# FPGAPower.net
KiCad netlist of a schematic drawn in Altium Designer
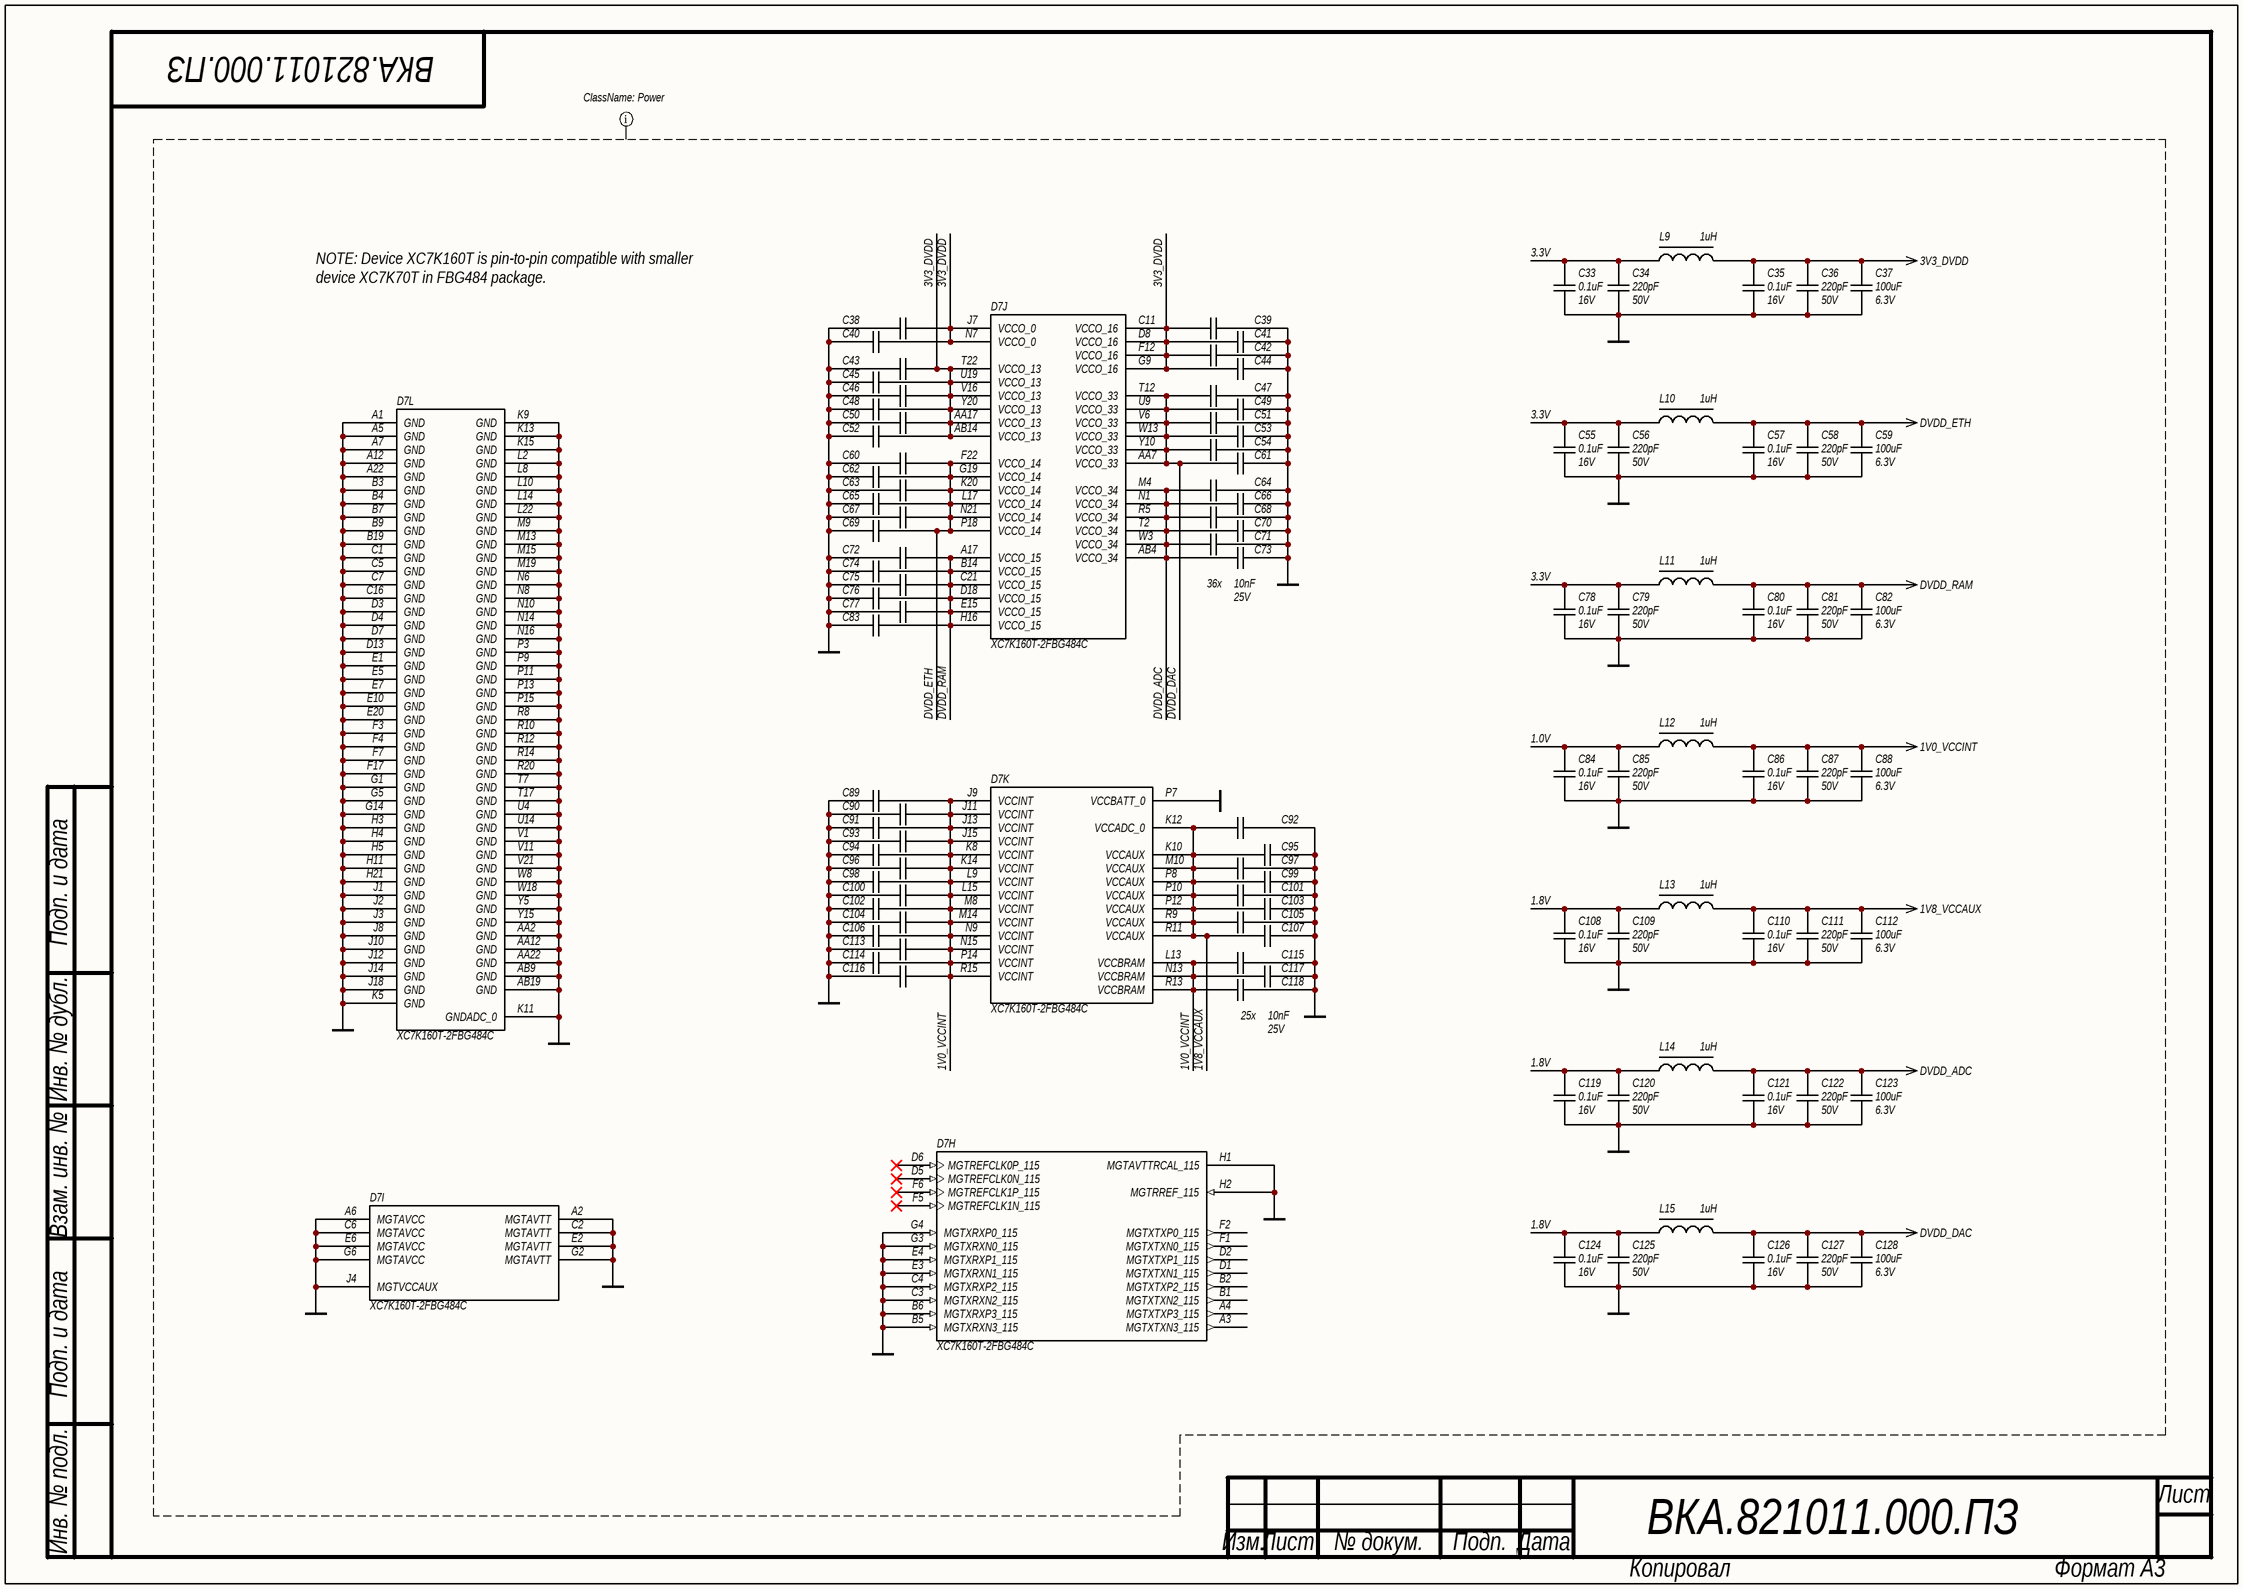
[diagram p0: FPGAPower.SchDoc]

(export (version "E")
  (design (tool "Eeschema 10.0.6"))
  (components
    (comp (ref "C33")
      (value "0.1uF")
      (footprint "C0603")
      (description "SMD Capacitor")
      (fields
        (field (name "MANUFACTURER") "Murata")
        (field (name "TOLERANCE") "10%")
        (field (name "VOLTAGE") "16V")
      )
      (libsource (lib "Kintex_SDR") (part "CAP"))
    )
    (comp (ref "C34")
      (value "220pF")
      (footprint "C0603")
      (description "SMD Capacitor")
      (fields
        (field (name "MANUFACTURER") "Murata")
        (field (name "TOLERANCE") "10%")
        (field (name "VOLTAGE") "50V")
      )
      (libsource (lib "Kintex_SDR") (part "CAP"))
    )
    (comp (ref "C35")
      (value "0.1uF")
      (footprint "C0603")
      (description "SMD Capacitor")
      (fields
        (field (name "MANUFACTURER") "Murata")
        (field (name "TOLERANCE") "10%")
        (field (name "VOLTAGE") "16V")
      )
      (libsource (lib "Kintex_SDR") (part "CAP"))
    )
    (comp (ref "C36")
      (value "220pF")
      (footprint "C0603")
      (description "SMD Capacitor")
      (fields
        (field (name "MANUFACTURER") "Murata")
        (field (name "TOLERANCE") "10%")
        (field (name "VOLTAGE") "50V")
      )
      (libsource (lib "Kintex_SDR") (part "CAP"))
    )
    (comp (ref "C37")
      (value "100uF")
      (footprint "C1210")
      (description "SMD Capacitor")
      (fields
        (field (name "MANUFACTURER") "Murata")
        (field (name "TOLERANCE") "20%")
        (field (name "VOLTAGE") "6.3V")
      )
      (libsource (lib "Kintex_SDR") (part "CAP uF"))
    )
    (comp (ref "C38")
      (value "CAP")
      (footprint "C0402")
      (description "SMD Capacitor")
      (fields (field (name "MANUFACTURER") "Murata") (field (name "TOLERANCE") "10%"))
      (libsource (lib "Kintex_SDR") (part "CAP"))
    )
    (comp (ref "C39")
      (value "CAP")
      (footprint "C0402")
      (description "SMD Capacitor")
      (fields (field (name "MANUFACTURER") "Murata") (field (name "TOLERANCE") "10%"))
      (libsource (lib "Kintex_SDR") (part "CAP"))
    )
    (comp (ref "C40")
      (value "CAP")
      (footprint "C0402")
      (description "SMD Capacitor")
      (fields (field (name "MANUFACTURER") "Murata") (field (name "TOLERANCE") "10%"))
      (libsource (lib "Kintex_SDR") (part "CAP"))
    )
    (comp (ref "C41")
      (value "CAP")
      (footprint "C0402")
      (description "SMD Capacitor")
      (fields (field (name "MANUFACTURER") "Murata") (field (name "TOLERANCE") "10%"))
      (libsource (lib "Kintex_SDR") (part "CAP"))
    )
    (comp (ref "C42")
      (value "CAP")
      (footprint "C0402")
      (description "SMD Capacitor")
      (fields (field (name "MANUFACTURER") "Murata") (field (name "TOLERANCE") "10%"))
      (libsource (lib "Kintex_SDR") (part "CAP"))
    )
    (comp (ref "C43")
      (value "CAP")
      (footprint "C0402")
      (description "SMD Capacitor")
      (fields (field (name "MANUFACTURER") "Murata") (field (name "TOLERANCE") "10%"))
      (libsource (lib "Kintex_SDR") (part "CAP"))
    )
    (comp (ref "C44")
      (value "CAP")
      (footprint "C0402")
      (description "SMD Capacitor")
      (fields (field (name "MANUFACTURER") "Murata") (field (name "TOLERANCE") "10%"))
      (libsource (lib "Kintex_SDR") (part "CAP"))
    )
    (comp (ref "C45")
      (value "CAP")
      (footprint "C0402")
      (description "SMD Capacitor")
      (fields (field (name "MANUFACTURER") "Murata") (field (name "TOLERANCE") "10%"))
      (libsource (lib "Kintex_SDR") (part "CAP"))
    )
    (comp (ref "C46")
      (value "CAP")
      (footprint "C0402")
      (description "SMD Capacitor")
      (fields (field (name "MANUFACTURER") "Murata") (field (name "TOLERANCE") "10%"))
      (libsource (lib "Kintex_SDR") (part "CAP"))
    )
    (comp (ref "C47")
      (value "CAP")
      (footprint "C0402")
      (description "SMD Capacitor")
      (fields (field (name "MANUFACTURER") "Murata") (field (name "TOLERANCE") "10%"))
      (libsource (lib "Kintex_SDR") (part "CAP"))
    )
    (comp (ref "C48")
      (value "CAP")
      (footprint "C0402")
      (description "SMD Capacitor")
      (fields (field (name "MANUFACTURER") "Murata") (field (name "TOLERANCE") "10%"))
      (libsource (lib "Kintex_SDR") (part "CAP"))
    )
    (comp (ref "C49")
      (value "CAP")
      (footprint "C0402")
      (description "SMD Capacitor")
      (fields (field (name "MANUFACTURER") "Murata") (field (name "TOLERANCE") "10%"))
      (libsource (lib "Kintex_SDR") (part "CAP"))
    )
    (comp (ref "C50")
      (value "CAP")
      (footprint "C0402")
      (description "SMD Capacitor")
      (fields (field (name "MANUFACTURER") "Murata") (field (name "TOLERANCE") "10%"))
      (libsource (lib "Kintex_SDR") (part "CAP"))
    )
    (comp (ref "C51")
      (value "CAP")
      (footprint "C0402")
      (description "SMD Capacitor")
      (fields (field (name "MANUFACTURER") "Murata") (field (name "TOLERANCE") "10%"))
      (libsource (lib "Kintex_SDR") (part "CAP"))
    )
    (comp (ref "C52")
      (value "CAP")
      (footprint "C0402")
      (description "SMD Capacitor")
      (fields (field (name "MANUFACTURER") "Murata") (field (name "TOLERANCE") "10%"))
      (libsource (lib "Kintex_SDR") (part "CAP"))
    )
    (comp (ref "C53")
      (value "CAP")
      (footprint "C0402")
      (description "SMD Capacitor")
      (fields (field (name "MANUFACTURER") "Murata") (field (name "TOLERANCE") "10%"))
      (libsource (lib "Kintex_SDR") (part "CAP"))
    )
    (comp (ref "C54")
      (value "CAP")
      (footprint "C0402")
      (description "SMD Capacitor")
      (fields (field (name "MANUFACTURER") "Murata") (field (name "TOLERANCE") "10%"))
      (libsource (lib "Kintex_SDR") (part "CAP"))
    )
    (comp (ref "C55")
      (value "0.1uF")
      (footprint "C0603")
      (description "SMD Capacitor")
      (fields
        (field (name "MANUFACTURER") "Murata")
        (field (name "TOLERANCE") "10%")
        (field (name "VOLTAGE") "16V")
      )
      (libsource (lib "Kintex_SDR") (part "CAP"))
    )
    (comp (ref "C56")
      (value "220pF")
      (footprint "C0603")
      (description "SMD Capacitor")
      (fields
        (field (name "MANUFACTURER") "Murata")
        (field (name "TOLERANCE") "10%")
        (field (name "VOLTAGE") "50V")
      )
      (libsource (lib "Kintex_SDR") (part "CAP"))
    )
    (comp (ref "C57")
      (value "0.1uF")
      (footprint "C0603")
      (description "SMD Capacitor")
      (fields
        (field (name "MANUFACTURER") "Murata")
        (field (name "TOLERANCE") "10%")
        (field (name "VOLTAGE") "16V")
      )
      (libsource (lib "Kintex_SDR") (part "CAP"))
    )
    (comp (ref "C58")
      (value "220pF")
      (footprint "C0603")
      (description "SMD Capacitor")
      (fields
        (field (name "MANUFACTURER") "Murata")
        (field (name "TOLERANCE") "10%")
        (field (name "VOLTAGE") "50V")
      )
      (libsource (lib "Kintex_SDR") (part "CAP"))
    )
    (comp (ref "C59")
      (value "100uF")
      (footprint "C1210")
      (description "SMD Capacitor")
      (fields
        (field (name "MANUFACTURER") "Murata")
        (field (name "TOLERANCE") "20%")
        (field (name "VOLTAGE") "6.3V")
      )
      (libsource (lib "Kintex_SDR") (part "CAP uF"))
    )
    (comp (ref "C60")
      (value "CAP")
      (footprint "C0402")
      (description "SMD Capacitor")
      (fields (field (name "MANUFACTURER") "Murata") (field (name "TOLERANCE") "10%"))
      (libsource (lib "Kintex_SDR") (part "CAP"))
    )
    (comp (ref "C61")
      (value "CAP")
      (footprint "C0402")
      (description "SMD Capacitor")
      (fields (field (name "MANUFACTURER") "Murata") (field (name "TOLERANCE") "10%"))
      (libsource (lib "Kintex_SDR") (part "CAP"))
    )
    (comp (ref "C62")
      (value "CAP")
      (footprint "C0402")
      (description "SMD Capacitor")
      (fields (field (name "MANUFACTURER") "Murata") (field (name "TOLERANCE") "10%"))
      (libsource (lib "Kintex_SDR") (part "CAP"))
    )
    (comp (ref "C63")
      (value "CAP")
      (footprint "C0402")
      (description "SMD Capacitor")
      (fields (field (name "MANUFACTURER") "Murata") (field (name "TOLERANCE") "10%"))
      (libsource (lib "Kintex_SDR") (part "CAP"))
    )
    (comp (ref "C64")
      (value "CAP")
      (footprint "C0402")
      (description "SMD Capacitor")
      (fields (field (name "MANUFACTURER") "Murata") (field (name "TOLERANCE") "10%"))
      (libsource (lib "Kintex_SDR") (part "CAP"))
    )
    (comp (ref "C65")
      (value "CAP")
      (footprint "C0402")
      (description "SMD Capacitor")
      (fields (field (name "MANUFACTURER") "Murata") (field (name "TOLERANCE") "10%"))
      (libsource (lib "Kintex_SDR") (part "CAP"))
    )
    (comp (ref "C66")
      (value "CAP")
      (footprint "C0402")
      (description "SMD Capacitor")
      (fields (field (name "MANUFACTURER") "Murata") (field (name "TOLERANCE") "10%"))
      (libsource (lib "Kintex_SDR") (part "CAP"))
    )
    (comp (ref "C67")
      (value "CAP")
      (footprint "C0402")
      (description "SMD Capacitor")
      (fields (field (name "MANUFACTURER") "Murata") (field (name "TOLERANCE") "10%"))
      (libsource (lib "Kintex_SDR") (part "CAP"))
    )
    (comp (ref "C68")
      (value "CAP")
      (footprint "C0402")
      (description "SMD Capacitor")
      (fields (field (name "MANUFACTURER") "Murata") (field (name "TOLERANCE") "10%"))
      (libsource (lib "Kintex_SDR") (part "CAP"))
    )
    (comp (ref "C69")
      (value "CAP")
      (footprint "C0402")
      (description "SMD Capacitor")
      (fields (field (name "MANUFACTURER") "Murata") (field (name "TOLERANCE") "10%"))
      (libsource (lib "Kintex_SDR") (part "CAP"))
    )
    (comp (ref "C70")
      (value "CAP")
      (footprint "C0402")
      (description "SMD Capacitor")
      (fields (field (name "MANUFACTURER") "Murata") (field (name "TOLERANCE") "10%"))
      (libsource (lib "Kintex_SDR") (part "CAP"))
    )
    (comp (ref "C71")
      (value "CAP")
      (footprint "C0402")
      (description "SMD Capacitor")
      (fields (field (name "MANUFACTURER") "Murata") (field (name "TOLERANCE") "10%"))
      (libsource (lib "Kintex_SDR") (part "CAP"))
    )
    (comp (ref "C72")
      (value "CAP")
      (footprint "C0402")
      (description "SMD Capacitor")
      (fields (field (name "MANUFACTURER") "Murata") (field (name "TOLERANCE") "10%"))
      (libsource (lib "Kintex_SDR") (part "CAP"))
    )
    (comp (ref "C73")
      (value "10nF")
      (footprint "C0402")
      (description "SMD Capacitor")
      (fields
        (field (name "MANUFACTURER") "Murata")
        (field (name "TOLERANCE") "10%")
        (field (name "VOLTAGE") "25V")
      )
      (libsource (lib "Kintex_SDR") (part "CAP"))
    )
    (comp (ref "C74")
      (value "CAP")
      (footprint "C0402")
      (description "SMD Capacitor")
      (fields (field (name "MANUFACTURER") "Murata") (field (name "TOLERANCE") "10%"))
      (libsource (lib "Kintex_SDR") (part "CAP"))
    )
    (comp (ref "C75")
      (value "CAP")
      (footprint "C0402")
      (description "SMD Capacitor")
      (fields (field (name "MANUFACTURER") "Murata") (field (name "TOLERANCE") "10%"))
      (libsource (lib "Kintex_SDR") (part "CAP"))
    )
    (comp (ref "C76")
      (value "CAP")
      (footprint "C0402")
      (description "SMD Capacitor")
      (fields (field (name "MANUFACTURER") "Murata") (field (name "TOLERANCE") "10%"))
      (libsource (lib "Kintex_SDR") (part "CAP"))
    )
    (comp (ref "C77")
      (value "CAP")
      (footprint "C0402")
      (description "SMD Capacitor")
      (fields (field (name "MANUFACTURER") "Murata") (field (name "TOLERANCE") "10%"))
      (libsource (lib "Kintex_SDR") (part "CAP"))
    )
    (comp (ref "C78")
      (value "0.1uF")
      (footprint "C0603")
      (description "SMD Capacitor")
      (fields
        (field (name "MANUFACTURER") "Murata")
        (field (name "TOLERANCE") "10%")
        (field (name "VOLTAGE") "16V")
      )
      (libsource (lib "Kintex_SDR") (part "CAP"))
    )
    (comp (ref "C79")
      (value "220pF")
      (footprint "C0603")
      (description "SMD Capacitor")
      (fields
        (field (name "MANUFACTURER") "Murata")
        (field (name "TOLERANCE") "10%")
        (field (name "VOLTAGE") "50V")
      )
      (libsource (lib "Kintex_SDR") (part "CAP"))
    )
    (comp (ref "C80")
      (value "0.1uF")
      (footprint "C0603")
      (description "SMD Capacitor")
      (fields
        (field (name "MANUFACTURER") "Murata")
        (field (name "TOLERANCE") "10%")
        (field (name "VOLTAGE") "16V")
      )
      (libsource (lib "Kintex_SDR") (part "CAP"))
    )
    (comp (ref "C81")
      (value "220pF")
      (footprint "C0603")
      (description "SMD Capacitor")
      (fields
        (field (name "MANUFACTURER") "Murata")
        (field (name "TOLERANCE") "10%")
        (field (name "VOLTAGE") "50V")
      )
      (libsource (lib "Kintex_SDR") (part "CAP"))
    )
    (comp (ref "C82")
      (value "100uF")
      (footprint "C1210")
      (description "SMD Capacitor")
      (fields
        (field (name "MANUFACTURER") "Murata")
        (field (name "TOLERANCE") "20%")
        (field (name "VOLTAGE") "6.3V")
      )
      (libsource (lib "Kintex_SDR") (part "CAP uF"))
    )
    (comp (ref "C83")
      (value "CAP")
      (footprint "C0402")
      (description "SMD Capacitor")
      (fields (field (name "MANUFACTURER") "Murata") (field (name "TOLERANCE") "10%"))
      (libsource (lib "Kintex_SDR") (part "CAP"))
    )
    (comp (ref "C84")
      (value "0.1uF")
      (footprint "C0603")
      (description "SMD Capacitor")
      (fields
        (field (name "MANUFACTURER") "Murata")
        (field (name "TOLERANCE") "10%")
        (field (name "VOLTAGE") "16V")
      )
      (libsource (lib "Kintex_SDR") (part "CAP"))
    )
    (comp (ref "C85")
      (value "220pF")
      (footprint "C0603")
      (description "SMD Capacitor")
      (fields
        (field (name "MANUFACTURER") "Murata")
        (field (name "TOLERANCE") "10%")
        (field (name "VOLTAGE") "50V")
      )
      (libsource (lib "Kintex_SDR") (part "CAP"))
    )
    (comp (ref "C86")
      (value "0.1uF")
      (footprint "C0603")
      (description "SMD Capacitor")
      (fields
        (field (name "MANUFACTURER") "Murata")
        (field (name "TOLERANCE") "10%")
        (field (name "VOLTAGE") "16V")
      )
      (libsource (lib "Kintex_SDR") (part "CAP"))
    )
    (comp (ref "C87")
      (value "220pF")
      (footprint "C0603")
      (description "SMD Capacitor")
      (fields
        (field (name "MANUFACTURER") "Murata")
        (field (name "TOLERANCE") "10%")
        (field (name "VOLTAGE") "50V")
      )
      (libsource (lib "Kintex_SDR") (part "CAP"))
    )
    (comp (ref "C88")
      (value "100uF")
      (footprint "C1210")
      (description "SMD Capacitor")
      (fields
        (field (name "MANUFACTURER") "Murata")
        (field (name "TOLERANCE") "20%")
        (field (name "VOLTAGE") "6.3V")
      )
      (libsource (lib "Kintex_SDR") (part "CAP uF"))
    )
    (comp (ref "C89")
      (value "CAP")
      (footprint "C0402")
      (description "SMD Capacitor")
      (fields (field (name "MANUFACTURER") "Murata") (field (name "TOLERANCE") "10%"))
      (libsource (lib "Kintex_SDR") (part "CAP"))
    )
    (comp (ref "C90")
      (value "CAP")
      (footprint "C0402")
      (description "SMD Capacitor")
      (fields (field (name "MANUFACTURER") "Murata") (field (name "TOLERANCE") "10%"))
      (libsource (lib "Kintex_SDR") (part "CAP"))
    )
    (comp (ref "C91")
      (value "CAP")
      (footprint "C0402")
      (description "SMD Capacitor")
      (fields (field (name "MANUFACTURER") "Murata") (field (name "TOLERANCE") "10%"))
      (libsource (lib "Kintex_SDR") (part "CAP"))
    )
    (comp (ref "C92")
      (value "CAP")
      (footprint "C0402")
      (description "SMD Capacitor")
      (fields (field (name "MANUFACTURER") "Murata") (field (name "TOLERANCE") "10%"))
      (libsource (lib "Kintex_SDR") (part "CAP"))
    )
    (comp (ref "C93")
      (value "CAP")
      (footprint "C0402")
      (description "SMD Capacitor")
      (fields (field (name "MANUFACTURER") "Murata") (field (name "TOLERANCE") "10%"))
      (libsource (lib "Kintex_SDR") (part "CAP"))
    )
    (comp (ref "C94")
      (value "CAP")
      (footprint "C0402")
      (description "SMD Capacitor")
      (fields (field (name "MANUFACTURER") "Murata") (field (name "TOLERANCE") "10%"))
      (libsource (lib "Kintex_SDR") (part "CAP"))
    )
    (comp (ref "C95")
      (value "CAP")
      (footprint "C0402")
      (description "SMD Capacitor")
      (fields (field (name "MANUFACTURER") "Murata") (field (name "TOLERANCE") "10%"))
      (libsource (lib "Kintex_SDR") (part "CAP"))
    )
    (comp (ref "C96")
      (value "CAP")
      (footprint "C0402")
      (description "SMD Capacitor")
      (fields (field (name "MANUFACTURER") "Murata") (field (name "TOLERANCE") "10%"))
      (libsource (lib "Kintex_SDR") (part "CAP"))
    )
    (comp (ref "C97")
      (value "CAP")
      (footprint "C0402")
      (description "SMD Capacitor")
      (fields (field (name "MANUFACTURER") "Murata") (field (name "TOLERANCE") "10%"))
      (libsource (lib "Kintex_SDR") (part "CAP"))
    )
    (comp (ref "C98")
      (value "CAP")
      (footprint "C0402")
      (description "SMD Capacitor")
      (fields (field (name "MANUFACTURER") "Murata") (field (name "TOLERANCE") "10%"))
      (libsource (lib "Kintex_SDR") (part "CAP"))
    )
    (comp (ref "C99")
      (value "CAP")
      (footprint "C0402")
      (description "SMD Capacitor")
      (fields (field (name "MANUFACTURER") "Murata") (field (name "TOLERANCE") "10%"))
      (libsource (lib "Kintex_SDR") (part "CAP"))
    )
    (comp (ref "C100")
      (value "CAP")
      (footprint "C0402")
      (description "SMD Capacitor")
      (fields (field (name "MANUFACTURER") "Murata") (field (name "TOLERANCE") "10%"))
      (libsource (lib "Kintex_SDR") (part "CAP"))
    )
    (comp (ref "C101")
      (value "CAP")
      (footprint "C0402")
      (description "SMD Capacitor")
      (fields (field (name "MANUFACTURER") "Murata") (field (name "TOLERANCE") "10%"))
      (libsource (lib "Kintex_SDR") (part "CAP"))
    )
    (comp (ref "C102")
      (value "CAP")
      (footprint "C0402")
      (description "SMD Capacitor")
      (fields (field (name "MANUFACTURER") "Murata") (field (name "TOLERANCE") "10%"))
      (libsource (lib "Kintex_SDR") (part "CAP"))
    )
    (comp (ref "C103")
      (value "CAP")
      (footprint "C0402")
      (description "SMD Capacitor")
      (fields (field (name "MANUFACTURER") "Murata") (field (name "TOLERANCE") "10%"))
      (libsource (lib "Kintex_SDR") (part "CAP"))
    )
    (comp (ref "C104")
      (value "CAP")
      (footprint "C0402")
      (description "SMD Capacitor")
      (fields (field (name "MANUFACTURER") "Murata") (field (name "TOLERANCE") "10%"))
      (libsource (lib "Kintex_SDR") (part "CAP"))
    )
    (comp (ref "C105")
      (value "CAP")
      (footprint "C0402")
      (description "SMD Capacitor")
      (fields (field (name "MANUFACTURER") "Murata") (field (name "TOLERANCE") "10%"))
      (libsource (lib "Kintex_SDR") (part "CAP"))
    )
    (comp (ref "C106")
      (value "CAP")
      (footprint "C0402")
      (description "SMD Capacitor")
      (fields (field (name "MANUFACTURER") "Murata") (field (name "TOLERANCE") "10%"))
      (libsource (lib "Kintex_SDR") (part "CAP"))
    )
    (comp (ref "C107")
      (value "CAP")
      (footprint "C0402")
      (description "SMD Capacitor")
      (fields (field (name "MANUFACTURER") "Murata") (field (name "TOLERANCE") "10%"))
      (libsource (lib "Kintex_SDR") (part "CAP"))
    )
    (comp (ref "C108")
      (value "0.1uF")
      (footprint "C0603")
      (description "SMD Capacitor")
      (fields
        (field (name "MANUFACTURER") "Murata")
        (field (name "TOLERANCE") "10%")
        (field (name "VOLTAGE") "16V")
      )
      (libsource (lib "Kintex_SDR") (part "CAP"))
    )
    (comp (ref "C109")
      (value "220pF")
      (footprint "C0603")
      (description "SMD Capacitor")
      (fields
        (field (name "MANUFACTURER") "Murata")
        (field (name "TOLERANCE") "10%")
        (field (name "VOLTAGE") "50V")
      )
      (libsource (lib "Kintex_SDR") (part "CAP"))
    )
    (comp (ref "C110")
      (value "0.1uF")
      (footprint "C0603")
      (description "SMD Capacitor")
      (fields
        (field (name "MANUFACTURER") "Murata")
        (field (name "TOLERANCE") "10%")
        (field (name "VOLTAGE") "16V")
      )
      (libsource (lib "Kintex_SDR") (part "CAP"))
    )
    (comp (ref "C111")
      (value "220pF")
      (footprint "C0603")
      (description "SMD Capacitor")
      (fields
        (field (name "MANUFACTURER") "Murata")
        (field (name "TOLERANCE") "10%")
        (field (name "VOLTAGE") "50V")
      )
      (libsource (lib "Kintex_SDR") (part "CAP"))
    )
    (comp (ref "C112")
      (value "100uF")
      (footprint "C1210")
      (description "SMD Capacitor")
      (fields
        (field (name "MANUFACTURER") "Murata")
        (field (name "TOLERANCE") "20%")
        (field (name "VOLTAGE") "6.3V")
      )
      (libsource (lib "Kintex_SDR") (part "CAP uF"))
    )
    (comp (ref "C113")
      (value "CAP")
      (footprint "C0402")
      (description "SMD Capacitor")
      (fields (field (name "MANUFACTURER") "Murata") (field (name "TOLERANCE") "10%"))
      (libsource (lib "Kintex_SDR") (part "CAP"))
    )
    (comp (ref "C114")
      (value "CAP")
      (footprint "C0402")
      (description "SMD Capacitor")
      (fields (field (name "MANUFACTURER") "Murata") (field (name "TOLERANCE") "10%"))
      (libsource (lib "Kintex_SDR") (part "CAP"))
    )
    (comp (ref "C115")
      (value "CAP")
      (footprint "C0402")
      (description "SMD Capacitor")
      (fields (field (name "MANUFACTURER") "Murata") (field (name "TOLERANCE") "10%"))
      (libsource (lib "Kintex_SDR") (part "CAP"))
    )
    (comp (ref "C116")
      (value "CAP")
      (footprint "C0402")
      (description "SMD Capacitor")
      (fields (field (name "MANUFACTURER") "Murata") (field (name "TOLERANCE") "10%"))
      (libsource (lib "Kintex_SDR") (part "CAP"))
    )
    (comp (ref "C117")
      (value "CAP")
      (footprint "C0402")
      (description "SMD Capacitor")
      (fields (field (name "MANUFACTURER") "Murata") (field (name "TOLERANCE") "10%"))
      (libsource (lib "Kintex_SDR") (part "CAP"))
    )
    (comp (ref "C118")
      (value "10nF")
      (footprint "C0402")
      (description "SMD Capacitor")
      (fields
        (field (name "MANUFACTURER") "Murata")
        (field (name "TOLERANCE") "10%")
        (field (name "VOLTAGE") "25V")
      )
      (libsource (lib "Kintex_SDR") (part "CAP"))
    )
    (comp (ref "C119")
      (value "0.1uF")
      (footprint "C0603")
      (description "SMD Capacitor")
      (fields
        (field (name "MANUFACTURER") "Murata")
        (field (name "TOLERANCE") "10%")
        (field (name "VOLTAGE") "16V")
      )
      (libsource (lib "Kintex_SDR") (part "CAP"))
    )
    (comp (ref "C120")
      (value "220pF")
      (footprint "C0603")
      (description "SMD Capacitor")
      (fields
        (field (name "MANUFACTURER") "Murata")
        (field (name "TOLERANCE") "10%")
        (field (name "VOLTAGE") "50V")
      )
      (libsource (lib "Kintex_SDR") (part "CAP"))
    )
    (comp (ref "C121")
      (value "0.1uF")
      (footprint "C0603")
      (description "SMD Capacitor")
      (fields
        (field (name "MANUFACTURER") "Murata")
        (field (name "TOLERANCE") "10%")
        (field (name "VOLTAGE") "16V")
      )
      (libsource (lib "Kintex_SDR") (part "CAP"))
    )
    (comp (ref "C122")
      (value "220pF")
      (footprint "C0603")
      (description "SMD Capacitor")
      (fields
        (field (name "MANUFACTURER") "Murata")
        (field (name "TOLERANCE") "10%")
        (field (name "VOLTAGE") "50V")
      )
      (libsource (lib "Kintex_SDR") (part "CAP"))
    )
    (comp (ref "C123")
      (value "100uF")
      (footprint "C1210")
      (description "SMD Capacitor")
      (fields
        (field (name "MANUFACTURER") "Murata")
        (field (name "TOLERANCE") "20%")
        (field (name "VOLTAGE") "6.3V")
      )
      (libsource (lib "Kintex_SDR") (part "CAP uF"))
    )
    (comp (ref "C124")
      (value "0.1uF")
      (footprint "C0603")
      (description "SMD Capacitor")
      (fields
        (field (name "MANUFACTURER") "Murata")
        (field (name "TOLERANCE") "10%")
        (field (name "VOLTAGE") "16V")
      )
      (libsource (lib "Kintex_SDR") (part "CAP"))
    )
    (comp (ref "C125")
      (value "220pF")
      (footprint "C0603")
      (description "SMD Capacitor")
      (fields
        (field (name "MANUFACTURER") "Murata")
        (field (name "TOLERANCE") "10%")
        (field (name "VOLTAGE") "50V")
      )
      (libsource (lib "Kintex_SDR") (part "CAP"))
    )
    (comp (ref "C126")
      (value "0.1uF")
      (footprint "C0603")
      (description "SMD Capacitor")
      (fields
        (field (name "MANUFACTURER") "Murata")
        (field (name "TOLERANCE") "10%")
        (field (name "VOLTAGE") "16V")
      )
      (libsource (lib "Kintex_SDR") (part "CAP"))
    )
    (comp (ref "C127")
      (value "220pF")
      (footprint "C0603")
      (description "SMD Capacitor")
      (fields
        (field (name "MANUFACTURER") "Murata")
        (field (name "TOLERANCE") "10%")
        (field (name "VOLTAGE") "50V")
      )
      (libsource (lib "Kintex_SDR") (part "CAP"))
    )
    (comp (ref "C128")
      (value "100uF")
      (footprint "C1210")
      (description "SMD Capacitor")
      (fields
        (field (name "MANUFACTURER") "Murata")
        (field (name "TOLERANCE") "20%")
        (field (name "VOLTAGE") "6.3V")
      )
      (libsource (lib "Kintex_SDR") (part "CAP uF"))
    )
    (comp (ref "D7")
      (value "XC7K160T-2FBG484C")
      (footprint "FBG484")
      (description "Xilinx 7-Series FPGA")
      (fields (field (name "MANUFACTURER") "Xilinx"))
      (libsource (lib "Kintex_SDR") (part "XC7K160T-2FBG484C"))
    )
    (comp (ref "L9")
      (value "1uH")
      (footprint "L1210_Murata LQH")
      (description "Inductor Power Lines")
      (fields (field (name "MANUFACTURER") "Murata") (field (name "TOLERANCE") "5%"))
      (libsource (lib "Kintex_SDR") (part "Inductor LF"))
    )
    (comp (ref "L10")
      (value "1uH")
      (footprint "L1210_Murata LQH")
      (description "Inductor Power Lines")
      (fields (field (name "MANUFACTURER") "Murata") (field (name "TOLERANCE") "5%"))
      (libsource (lib "Kintex_SDR") (part "Inductor LF"))
    )
    (comp (ref "L11")
      (value "1uH")
      (footprint "L1210_Murata LQH")
      (description "Inductor Power Lines")
      (fields (field (name "MANUFACTURER") "Murata") (field (name "TOLERANCE") "5%"))
      (libsource (lib "Kintex_SDR") (part "Inductor LF"))
    )
    (comp (ref "L12")
      (value "1uH")
      (footprint "L1210_Murata LQH")
      (description "Inductor Power Lines")
      (fields (field (name "MANUFACTURER") "Murata") (field (name "TOLERANCE") "5%"))
      (libsource (lib "Kintex_SDR") (part "Inductor LF"))
    )
    (comp (ref "L13")
      (value "1uH")
      (footprint "L1210_Murata LQH")
      (description "Inductor Power Lines")
      (fields (field (name "MANUFACTURER") "Murata") (field (name "TOLERANCE") "5%"))
      (libsource (lib "Kintex_SDR") (part "Inductor LF"))
    )
    (comp (ref "L14")
      (value "1uH")
      (footprint "L1210_Murata LQH")
      (description "Inductor Power Lines")
      (fields (field (name "MANUFACTURER") "Murata") (field (name "TOLERANCE") "5%"))
      (libsource (lib "Kintex_SDR") (part "Inductor LF"))
    )
    (comp (ref "L15")
      (value "1uH")
      (footprint "L1210_Murata LQH")
      (description "Inductor Power Lines")
      (fields (field (name "MANUFACTURER") "Murata") (field (name "TOLERANCE") "5%"))
      (libsource (lib "Kintex_SDR") (part "Inductor LF"))
    )
  )
  (nets
    (net (code "1") (name "/1.0V") (class "Default")
      (node (ref "C84") (pin "2") (pinfunction "2_2") (pintype "passive"))
      (node (ref "C85") (pin "2") (pinfunction "2_2") (pintype "passive"))
      (node (ref "L12") (pin "1") (pinfunction "1_1") (pintype "passive"))
    )
    (net (code "2") (name "/1.8V") (class "Default")
      (node (ref "C108") (pin "2") (pinfunction "2_2") (pintype "passive"))
      (node (ref "C109") (pin "2") (pinfunction "2_2") (pintype "passive"))
      (node (ref "C119") (pin "2") (pinfunction "2_2") (pintype "passive"))
      (node (ref "C120") (pin "2") (pinfunction "2_2") (pintype "passive"))
      (node (ref "C124") (pin "2") (pinfunction "2_2") (pintype "passive"))
      (node (ref "C125") (pin "2") (pinfunction "2_2") (pintype "passive"))
      (node (ref "L13") (pin "1") (pinfunction "1_1") (pintype "passive"))
      (node (ref "L14") (pin "1") (pinfunction "1_1") (pintype "passive"))
      (node (ref "L15") (pin "1") (pinfunction "1_1") (pintype "passive"))
    )
    (net (code "3") (name "/3.3V") (class "Default")
      (node (ref "C33") (pin "2") (pinfunction "2_2") (pintype "passive"))
      (node (ref "C34") (pin "2") (pinfunction "2_2") (pintype "passive"))
      (node (ref "C55") (pin "2") (pinfunction "2_2") (pintype "passive"))
      (node (ref "C56") (pin "2") (pinfunction "2_2") (pintype "passive"))
      (node (ref "C78") (pin "2") (pinfunction "2_2") (pintype "passive"))
      (node (ref "C79") (pin "2") (pinfunction "2_2") (pintype "passive"))
      (node (ref "L10") (pin "1") (pinfunction "1_1") (pintype "passive"))
      (node (ref "L11") (pin "1") (pinfunction "1_1") (pintype "passive"))
      (node (ref "L9") (pin "1") (pinfunction "1_1") (pintype "passive"))
    )
    (net (code "4") (name "1V0_VCCINT") (class "Default")
      (node (ref "C100") (pin "1") (pinfunction "1_1") (pintype "passive"))
      (node (ref "C102") (pin "1") (pinfunction "1_1") (pintype "passive"))
      (node (ref "C104") (pin "1") (pinfunction "1_1") (pintype "passive"))
      (node (ref "C106") (pin "1") (pinfunction "1_1") (pintype "passive"))
      (node (ref "C113") (pin "1") (pinfunction "1_1") (pintype "passive"))
      (node (ref "C114") (pin "1") (pinfunction "1_1") (pintype "passive"))
      (node (ref "C115") (pin "2") (pinfunction "2_2") (pintype "passive"))
      (node (ref "C116") (pin "1") (pinfunction "1_1") (pintype "passive"))
      (node (ref "C117") (pin "2") (pinfunction "2_2") (pintype "passive"))
      (node (ref "C118") (pin "2") (pinfunction "2_2") (pintype "passive"))
      (node (ref "C86") (pin "2") (pinfunction "2_2") (pintype "passive"))
      (node (ref "C87") (pin "2") (pinfunction "2_2") (pintype "passive"))
      (node (ref "C88") (pin "2") (pinfunction "2_2") (pintype "passive"))
      (node (ref "C89") (pin "1") (pinfunction "1_1") (pintype "passive"))
      (node (ref "C90") (pin "1") (pinfunction "1_1") (pintype "passive"))
      (node (ref "C91") (pin "1") (pinfunction "1_1") (pintype "passive"))
      (node (ref "C93") (pin "1") (pinfunction "1_1") (pintype "passive"))
      (node (ref "C94") (pin "1") (pinfunction "1_1") (pintype "passive"))
      (node (ref "C96") (pin "1") (pinfunction "1_1") (pintype "passive"))
      (node (ref "C98") (pin "1") (pinfunction "1_1") (pintype "passive"))
      (node (ref "D7") (pin "J11") (pinfunction "VCCINT_J11") (pintype "power_in"))
      (node (ref "D7") (pin "J13") (pinfunction "VCCINT_J13") (pintype "power_in"))
      (node (ref "D7") (pin "J15") (pinfunction "VCCINT_J15") (pintype "power_in"))
      (node (ref "D7") (pin "J9") (pinfunction "VCCINT_J9") (pintype "power_in"))
      (node (ref "D7") (pin "K14") (pinfunction "VCCINT_K14") (pintype "power_in"))
      (node (ref "D7") (pin "K8") (pinfunction "VCCINT_K8") (pintype "power_in"))
      (node (ref "D7") (pin "L13") (pinfunction "VCCBRAM_L13") (pintype "power_in"))
      (node (ref "D7") (pin "L15") (pinfunction "VCCINT_L15") (pintype "power_in"))
      (node (ref "D7") (pin "L9") (pinfunction "VCCINT_L9") (pintype "power_in"))
      (node (ref "D7") (pin "M14") (pinfunction "VCCINT_M14") (pintype "power_in"))
      (node (ref "D7") (pin "M8") (pinfunction "VCCINT_M8") (pintype "power_in"))
      (node (ref "D7") (pin "N13") (pinfunction "VCCBRAM_N13") (pintype "power_in"))
      (node (ref "D7") (pin "N15") (pinfunction "VCCINT_N15") (pintype "power_in"))
      (node (ref "D7") (pin "N9") (pinfunction "VCCINT_N9") (pintype "power_in"))
      (node (ref "D7") (pin "P14") (pinfunction "VCCINT_P14") (pintype "power_in"))
      (node (ref "D7") (pin "R13") (pinfunction "VCCBRAM_R13") (pintype "power_in"))
      (node (ref "D7") (pin "R15") (pinfunction "VCCINT_R15") (pintype "power_in"))
      (node (ref "L12") (pin "2") (pinfunction "2_2") (pintype "passive"))
    )
    (net (code "5") (name "1V8_VCCAUX") (class "Default")
      (node (ref "C101") (pin "2") (pinfunction "2_2") (pintype "passive"))
      (node (ref "C103") (pin "2") (pinfunction "2_2") (pintype "passive"))
      (node (ref "C105") (pin "2") (pinfunction "2_2") (pintype "passive"))
      (node (ref "C107") (pin "2") (pinfunction "2_2") (pintype "passive"))
      (node (ref "C110") (pin "2") (pinfunction "2_2") (pintype "passive"))
      (node (ref "C111") (pin "2") (pinfunction "2_2") (pintype "passive"))
      (node (ref "C112") (pin "2") (pinfunction "2_2") (pintype "passive"))
      (node (ref "C92") (pin "2") (pinfunction "2_2") (pintype "passive"))
      (node (ref "C95") (pin "2") (pinfunction "2_2") (pintype "passive"))
      (node (ref "C97") (pin "2") (pinfunction "2_2") (pintype "passive"))
      (node (ref "C99") (pin "2") (pinfunction "2_2") (pintype "passive"))
      (node (ref "D7") (pin "K10") (pinfunction "VCCAUX_K10") (pintype "power_in"))
      (node (ref "D7") (pin "K12") (pinfunction "VCCADC_0_K12") (pintype "power_in"))
      (node (ref "D7") (pin "M10") (pinfunction "VCCAUX_M10") (pintype "power_in"))
      (node (ref "D7") (pin "P10") (pinfunction "VCCAUX_P10") (pintype "power_in"))
      (node (ref "D7") (pin "P12") (pinfunction "VCCAUX_P12") (pintype "power_in"))
      (node (ref "D7") (pin "P8") (pinfunction "VCCAUX_P8") (pintype "power_in"))
      (node (ref "D7") (pin "R11") (pinfunction "VCCAUX_R11") (pintype "power_in"))
      (node (ref "D7") (pin "R9") (pinfunction "VCCAUX_R9") (pintype "power_in"))
      (node (ref "L13") (pin "2") (pinfunction "2_2") (pintype "passive"))
    )
    (net (code "6") (name "3V3_DVDD") (class "Default")
      (node (ref "C35") (pin "2") (pinfunction "2_2") (pintype "passive"))
      (node (ref "C36") (pin "2") (pinfunction "2_2") (pintype "passive"))
      (node (ref "C37") (pin "2") (pinfunction "2_2") (pintype "passive"))
      (node (ref "C38") (pin "1") (pinfunction "1_1") (pintype "passive"))
      (node (ref "C39") (pin "2") (pinfunction "2_2") (pintype "passive"))
      (node (ref "C40") (pin "1") (pinfunction "1_1") (pintype "passive"))
      (node (ref "C41") (pin "2") (pinfunction "2_2") (pintype "passive"))
      (node (ref "C42") (pin "2") (pinfunction "2_2") (pintype "passive"))
      (node (ref "C43") (pin "1") (pinfunction "1_1") (pintype "passive"))
      (node (ref "C44") (pin "2") (pinfunction "2_2") (pintype "passive"))
      (node (ref "C45") (pin "1") (pinfunction "1_1") (pintype "passive"))
      (node (ref "C46") (pin "1") (pinfunction "1_1") (pintype "passive"))
      (node (ref "C48") (pin "1") (pinfunction "1_1") (pintype "passive"))
      (node (ref "C50") (pin "1") (pinfunction "1_1") (pintype "passive"))
      (node (ref "C52") (pin "1") (pinfunction "1_1") (pintype "passive"))
      (node (ref "D7") (pin "AA17") (pinfunction "VCCO_13_AA17") (pintype "power_in"))
      (node (ref "D7") (pin "AB14") (pinfunction "VCCO_13_AB14") (pintype "power_in"))
      (node (ref "D7") (pin "C11") (pinfunction "VCCO_16_C11") (pintype "power_in"))
      (node (ref "D7") (pin "D8") (pinfunction "VCCO_16_D8") (pintype "power_in"))
      (node (ref "D7") (pin "F12") (pinfunction "VCCO_16_F12") (pintype "power_in"))
      (node (ref "D7") (pin "G9") (pinfunction "VCCO_16_G9") (pintype "power_in"))
      (node (ref "D7") (pin "J7") (pinfunction "VCCO_0_J7") (pintype "power_in"))
      (node (ref "D7") (pin "N7") (pinfunction "VCCO_0_N7") (pintype "power_in"))
      (node (ref "D7") (pin "T22") (pinfunction "VCCO_13_T22") (pintype "power_in"))
      (node (ref "D7") (pin "U19") (pinfunction "VCCO_13_U19") (pintype "power_in"))
      (node (ref "D7") (pin "V16") (pinfunction "VCCO_13_V16") (pintype "power_in"))
      (node (ref "D7") (pin "Y20") (pinfunction "VCCO_13_Y20") (pintype "power_in"))
      (node (ref "L9") (pin "2") (pinfunction "2_2") (pintype "passive"))
    )
    (net (code "7") (name "DVDD_ADC") (class "Default")
      (node (ref "C121") (pin "2") (pinfunction "2_2") (pintype "passive"))
      (node (ref "C122") (pin "2") (pinfunction "2_2") (pintype "passive"))
      (node (ref "C123") (pin "2") (pinfunction "2_2") (pintype "passive"))
      (node (ref "C64") (pin "2") (pinfunction "2_2") (pintype "passive"))
      (node (ref "C66") (pin "2") (pinfunction "2_2") (pintype "passive"))
      (node (ref "C68") (pin "2") (pinfunction "2_2") (pintype "passive"))
      (node (ref "C70") (pin "2") (pinfunction "2_2") (pintype "passive"))
      (node (ref "C71") (pin "2") (pinfunction "2_2") (pintype "passive"))
      (node (ref "C73") (pin "2") (pinfunction "2_2") (pintype "passive"))
      (node (ref "D7") (pin "AB4") (pinfunction "VCCO_34_AB4") (pintype "power_in"))
      (node (ref "D7") (pin "M4") (pinfunction "VCCO_34_M4") (pintype "power_in"))
      (node (ref "D7") (pin "N1") (pinfunction "VCCO_34_N1") (pintype "power_in"))
      (node (ref "D7") (pin "R5") (pinfunction "VCCO_34_R5") (pintype "power_in"))
      (node (ref "D7") (pin "T2") (pinfunction "VCCO_34_T2") (pintype "power_in"))
      (node (ref "D7") (pin "W3") (pinfunction "VCCO_34_W3") (pintype "power_in"))
      (node (ref "L14") (pin "2") (pinfunction "2_2") (pintype "passive"))
    )
    (net (code "8") (name "DVDD_DAC") (class "Default")
      (node (ref "C126") (pin "2") (pinfunction "2_2") (pintype "passive"))
      (node (ref "C127") (pin "2") (pinfunction "2_2") (pintype "passive"))
      (node (ref "C128") (pin "2") (pinfunction "2_2") (pintype "passive"))
      (node (ref "C47") (pin "2") (pinfunction "2_2") (pintype "passive"))
      (node (ref "C49") (pin "2") (pinfunction "2_2") (pintype "passive"))
      (node (ref "C51") (pin "2") (pinfunction "2_2") (pintype "passive"))
      (node (ref "C53") (pin "2") (pinfunction "2_2") (pintype "passive"))
      (node (ref "C54") (pin "2") (pinfunction "2_2") (pintype "passive"))
      (node (ref "C61") (pin "2") (pinfunction "2_2") (pintype "passive"))
      (node (ref "D7") (pin "AA7") (pinfunction "VCCO_33_AA7") (pintype "power_in"))
      (node (ref "D7") (pin "T12") (pinfunction "VCCO_33_T12") (pintype "power_in"))
      (node (ref "D7") (pin "U9") (pinfunction "VCCO_33_U9") (pintype "power_in"))
      (node (ref "D7") (pin "V6") (pinfunction "VCCO_33_V6") (pintype "power_in"))
      (node (ref "D7") (pin "W13") (pinfunction "VCCO_33_W13") (pintype "power_in"))
      (node (ref "D7") (pin "Y10") (pinfunction "VCCO_33_Y10") (pintype "power_in"))
      (node (ref "L15") (pin "2") (pinfunction "2_2") (pintype "passive"))
    )
    (net (code "9") (name "DVDD_ETH") (class "Default")
      (node (ref "C57") (pin "2") (pinfunction "2_2") (pintype "passive"))
      (node (ref "C58") (pin "2") (pinfunction "2_2") (pintype "passive"))
      (node (ref "C59") (pin "2") (pinfunction "2_2") (pintype "passive"))
      (node (ref "C60") (pin "1") (pinfunction "1_1") (pintype "passive"))
      (node (ref "C62") (pin "1") (pinfunction "1_1") (pintype "passive"))
      (node (ref "C63") (pin "1") (pinfunction "1_1") (pintype "passive"))
      (node (ref "C65") (pin "1") (pinfunction "1_1") (pintype "passive"))
      (node (ref "C67") (pin "1") (pinfunction "1_1") (pintype "passive"))
      (node (ref "C69") (pin "1") (pinfunction "1_1") (pintype "passive"))
      (node (ref "D7") (pin "F22") (pinfunction "VCCO_14_F22") (pintype "power_in"))
      (node (ref "D7") (pin "G19") (pinfunction "VCCO_14_G19") (pintype "power_in"))
      (node (ref "D7") (pin "K20") (pinfunction "VCCO_14_K20") (pintype "power_in"))
      (node (ref "D7") (pin "L17") (pinfunction "VCCO_14_L17") (pintype "power_in"))
      (node (ref "D7") (pin "N21") (pinfunction "VCCO_14_N21") (pintype "power_in"))
      (node (ref "D7") (pin "P18") (pinfunction "VCCO_14_P18") (pintype "power_in"))
      (node (ref "L10") (pin "2") (pinfunction "2_2") (pintype "passive"))
    )
    (net (code "10") (name "DVDD_RAM") (class "Default")
      (node (ref "C72") (pin "1") (pinfunction "1_1") (pintype "passive"))
      (node (ref "C74") (pin "1") (pinfunction "1_1") (pintype "passive"))
      (node (ref "C75") (pin "1") (pinfunction "1_1") (pintype "passive"))
      (node (ref "C76") (pin "1") (pinfunction "1_1") (pintype "passive"))
      (node (ref "C77") (pin "1") (pinfunction "1_1") (pintype "passive"))
      (node (ref "C80") (pin "2") (pinfunction "2_2") (pintype "passive"))
      (node (ref "C81") (pin "2") (pinfunction "2_2") (pintype "passive"))
      (node (ref "C82") (pin "2") (pinfunction "2_2") (pintype "passive"))
      (node (ref "C83") (pin "1") (pinfunction "1_1") (pintype "passive"))
      (node (ref "D7") (pin "A17") (pinfunction "VCCO_15_A17") (pintype "power_in"))
      (node (ref "D7") (pin "B14") (pinfunction "VCCO_15_B14") (pintype "power_in"))
      (node (ref "D7") (pin "C21") (pinfunction "VCCO_15_C21") (pintype "power_in"))
      (node (ref "D7") (pin "D18") (pinfunction "VCCO_15_D18") (pintype "power_in"))
      (node (ref "D7") (pin "E15") (pinfunction "VCCO_15_E15") (pintype "power_in"))
      (node (ref "D7") (pin "H16") (pinfunction "VCCO_15_H16") (pintype "power_in"))
      (node (ref "L11") (pin "2") (pinfunction "2_2") (pintype "passive"))
    )
    (net (code "11") (name "GND") (class "Default")
      (node (ref "C100") (pin "2") (pinfunction "2_2") (pintype "passive"))
      (node (ref "C101") (pin "1") (pinfunction "1_1") (pintype "passive"))
      (node (ref "C102") (pin "2") (pinfunction "2_2") (pintype "passive"))
      (node (ref "C103") (pin "1") (pinfunction "1_1") (pintype "passive"))
      (node (ref "C104") (pin "2") (pinfunction "2_2") (pintype "passive"))
      (node (ref "C105") (pin "1") (pinfunction "1_1") (pintype "passive"))
      (node (ref "C106") (pin "2") (pinfunction "2_2") (pintype "passive"))
      (node (ref "C107") (pin "1") (pinfunction "1_1") (pintype "passive"))
      (node (ref "C108") (pin "1") (pinfunction "1_1") (pintype "passive"))
      (node (ref "C109") (pin "1") (pinfunction "1_1") (pintype "passive"))
      (node (ref "C110") (pin "1") (pinfunction "1_1") (pintype "passive"))
      (node (ref "C111") (pin "1") (pinfunction "1_1") (pintype "passive"))
      (node (ref "C112") (pin "1") (pinfunction "1_1") (pintype "passive"))
      (node (ref "C113") (pin "2") (pinfunction "2_2") (pintype "passive"))
      (node (ref "C114") (pin "2") (pinfunction "2_2") (pintype "passive"))
      (node (ref "C115") (pin "1") (pinfunction "1_1") (pintype "passive"))
      (node (ref "C116") (pin "2") (pinfunction "2_2") (pintype "passive"))
      (node (ref "C117") (pin "1") (pinfunction "1_1") (pintype "passive"))
      (node (ref "C118") (pin "1") (pinfunction "1_1") (pintype "passive"))
      (node (ref "C119") (pin "1") (pinfunction "1_1") (pintype "passive"))
      (node (ref "C120") (pin "1") (pinfunction "1_1") (pintype "passive"))
      (node (ref "C121") (pin "1") (pinfunction "1_1") (pintype "passive"))
      (node (ref "C122") (pin "1") (pinfunction "1_1") (pintype "passive"))
      (node (ref "C123") (pin "1") (pinfunction "1_1") (pintype "passive"))
      (node (ref "C124") (pin "1") (pinfunction "1_1") (pintype "passive"))
      (node (ref "C125") (pin "1") (pinfunction "1_1") (pintype "passive"))
      (node (ref "C126") (pin "1") (pinfunction "1_1") (pintype "passive"))
      (node (ref "C127") (pin "1") (pinfunction "1_1") (pintype "passive"))
      (node (ref "C128") (pin "1") (pinfunction "1_1") (pintype "passive"))
      (node (ref "C33") (pin "1") (pinfunction "1_1") (pintype "passive"))
      (node (ref "C34") (pin "1") (pinfunction "1_1") (pintype "passive"))
      (node (ref "C35") (pin "1") (pinfunction "1_1") (pintype "passive"))
      (node (ref "C36") (pin "1") (pinfunction "1_1") (pintype "passive"))
      (node (ref "C37") (pin "1") (pinfunction "1_1") (pintype "passive"))
      (node (ref "C38") (pin "2") (pinfunction "2_2") (pintype "passive"))
      (node (ref "C39") (pin "1") (pinfunction "1_1") (pintype "passive"))
      (node (ref "C40") (pin "2") (pinfunction "2_2") (pintype "passive"))
      (node (ref "C41") (pin "1") (pinfunction "1_1") (pintype "passive"))
      (node (ref "C42") (pin "1") (pinfunction "1_1") (pintype "passive"))
      (node (ref "C43") (pin "2") (pinfunction "2_2") (pintype "passive"))
      (node (ref "C44") (pin "1") (pinfunction "1_1") (pintype "passive"))
      (node (ref "C45") (pin "2") (pinfunction "2_2") (pintype "passive"))
      (node (ref "C46") (pin "2") (pinfunction "2_2") (pintype "passive"))
      (node (ref "C47") (pin "1") (pinfunction "1_1") (pintype "passive"))
      (node (ref "C48") (pin "2") (pinfunction "2_2") (pintype "passive"))
      (node (ref "C49") (pin "1") (pinfunction "1_1") (pintype "passive"))
      (node (ref "C50") (pin "2") (pinfunction "2_2") (pintype "passive"))
      (node (ref "C51") (pin "1") (pinfunction "1_1") (pintype "passive"))
      (node (ref "C52") (pin "2") (pinfunction "2_2") (pintype "passive"))
      (node (ref "C53") (pin "1") (pinfunction "1_1") (pintype "passive"))
      (node (ref "C54") (pin "1") (pinfunction "1_1") (pintype "passive"))
      (node (ref "C55") (pin "1") (pinfunction "1_1") (pintype "passive"))
      (node (ref "C56") (pin "1") (pinfunction "1_1") (pintype "passive"))
      (node (ref "C57") (pin "1") (pinfunction "1_1") (pintype "passive"))
      (node (ref "C58") (pin "1") (pinfunction "1_1") (pintype "passive"))
      (node (ref "C59") (pin "1") (pinfunction "1_1") (pintype "passive"))
      (node (ref "C60") (pin "2") (pinfunction "2_2") (pintype "passive"))
      (node (ref "C61") (pin "1") (pinfunction "1_1") (pintype "passive"))
      (node (ref "C62") (pin "2") (pinfunction "2_2") (pintype "passive"))
      (node (ref "C63") (pin "2") (pinfunction "2_2") (pintype "passive"))
      (node (ref "C64") (pin "1") (pinfunction "1_1") (pintype "passive"))
      (node (ref "C65") (pin "2") (pinfunction "2_2") (pintype "passive"))
      (node (ref "C66") (pin "1") (pinfunction "1_1") (pintype "passive"))
      (node (ref "C67") (pin "2") (pinfunction "2_2") (pintype "passive"))
      (node (ref "C68") (pin "1") (pinfunction "1_1") (pintype "passive"))
      (node (ref "C69") (pin "2") (pinfunction "2_2") (pintype "passive"))
      (node (ref "C70") (pin "1") (pinfunction "1_1") (pintype "passive"))
      (node (ref "C71") (pin "1") (pinfunction "1_1") (pintype "passive"))
      (node (ref "C72") (pin "2") (pinfunction "2_2") (pintype "passive"))
      (node (ref "C73") (pin "1") (pinfunction "1_1") (pintype "passive"))
      (node (ref "C74") (pin "2") (pinfunction "2_2") (pintype "passive"))
      (node (ref "C75") (pin "2") (pinfunction "2_2") (pintype "passive"))
      (node (ref "C76") (pin "2") (pinfunction "2_2") (pintype "passive"))
      (node (ref "C77") (pin "2") (pinfunction "2_2") (pintype "passive"))
      (node (ref "C78") (pin "1") (pinfunction "1_1") (pintype "passive"))
      (node (ref "C79") (pin "1") (pinfunction "1_1") (pintype "passive"))
      (node (ref "C80") (pin "1") (pinfunction "1_1") (pintype "passive"))
      (node (ref "C81") (pin "1") (pinfunction "1_1") (pintype "passive"))
      (node (ref "C82") (pin "1") (pinfunction "1_1") (pintype "passive"))
      (node (ref "C83") (pin "2") (pinfunction "2_2") (pintype "passive"))
      (node (ref "C84") (pin "1") (pinfunction "1_1") (pintype "passive"))
      (node (ref "C85") (pin "1") (pinfunction "1_1") (pintype "passive"))
      (node (ref "C86") (pin "1") (pinfunction "1_1") (pintype "passive"))
      (node (ref "C87") (pin "1") (pinfunction "1_1") (pintype "passive"))
      (node (ref "C88") (pin "1") (pinfunction "1_1") (pintype "passive"))
      (node (ref "C89") (pin "2") (pinfunction "2_2") (pintype "passive"))
      (node (ref "C90") (pin "2") (pinfunction "2_2") (pintype "passive"))
      (node (ref "C91") (pin "2") (pinfunction "2_2") (pintype "passive"))
      (node (ref "C92") (pin "1") (pinfunction "1_1") (pintype "passive"))
      (node (ref "C93") (pin "2") (pinfunction "2_2") (pintype "passive"))
      (node (ref "C94") (pin "2") (pinfunction "2_2") (pintype "passive"))
      (node (ref "C95") (pin "1") (pinfunction "1_1") (pintype "passive"))
      (node (ref "C96") (pin "2") (pinfunction "2_2") (pintype "passive"))
      (node (ref "C97") (pin "1") (pinfunction "1_1") (pintype "passive"))
      (node (ref "C98") (pin "2") (pinfunction "2_2") (pintype "passive"))
      (node (ref "C99") (pin "1") (pinfunction "1_1") (pintype "passive"))
      (node (ref "D7") (pin "A1") (pinfunction "GND_A1") (pintype "power_in"))
      (node (ref "D7") (pin "A12") (pinfunction "GND_A12") (pintype "power_in"))
      (node (ref "D7") (pin "A2") (pinfunction "MGTAVTT_A2") (pintype "power_in"))
      (node (ref "D7") (pin "A22") (pinfunction "GND_A22") (pintype "power_in"))
      (node (ref "D7") (pin "A5") (pinfunction "GND_A5") (pintype "power_in"))
      (node (ref "D7") (pin "A6") (pinfunction "MGTAVCC_A6") (pintype "power_in"))
      (node (ref "D7") (pin "A7") (pinfunction "GND_A7") (pintype "power_in"))
      (node (ref "D7") (pin "AA12") (pinfunction "GND_AA12") (pintype "power_in"))
      (node (ref "D7") (pin "AA2") (pinfunction "GND_AA2") (pintype "power_in"))
      (node (ref "D7") (pin "AA22") (pinfunction "GND_AA22") (pintype "power_in"))
      (node (ref "D7") (pin "AB19") (pinfunction "GND_AB19") (pintype "power_in"))
      (node (ref "D7") (pin "AB9") (pinfunction "GND_AB9") (pintype "power_in"))
      (node (ref "D7") (pin "B19") (pinfunction "GND_B19") (pintype "power_in"))
      (node (ref "D7") (pin "B3") (pinfunction "GND_B3") (pintype "power_in"))
      (node (ref "D7") (pin "B4") (pinfunction "GND_B4") (pintype "power_in"))
      (node (ref "D7") (pin "B5") (pinfunction "MGTXRXN3_115_B5") (pintype "input"))
      (node (ref "D7") (pin "B6") (pinfunction "MGTXRXP3_115_B6") (pintype "input"))
      (node (ref "D7") (pin "B7") (pinfunction "GND_B7") (pintype "power_in"))
      (node (ref "D7") (pin "B9") (pinfunction "GND_B9") (pintype "power_in"))
      (node (ref "D7") (pin "C1") (pinfunction "GND_C1") (pintype "power_in"))
      (node (ref "D7") (pin "C16") (pinfunction "GND_C16") (pintype "power_in"))
      (node (ref "D7") (pin "C2") (pinfunction "MGTAVTT_C2") (pintype "power_in"))
      (node (ref "D7") (pin "C3") (pinfunction "MGTXRXN2_115_C3") (pintype "input"))
      (node (ref "D7") (pin "C4") (pinfunction "MGTXRXP2_115_C4") (pintype "input"))
      (node (ref "D7") (pin "C5") (pinfunction "GND_C5") (pintype "power_in"))
      (node (ref "D7") (pin "C6") (pinfunction "MGTAVCC_C6") (pintype "power_in"))
      (node (ref "D7") (pin "C7") (pinfunction "GND_C7") (pintype "power_in"))
      (node (ref "D7") (pin "D13") (pinfunction "GND_D13") (pintype "power_in"))
      (node (ref "D7") (pin "D3") (pinfunction "GND_D3") (pintype "power_in"))
      (node (ref "D7") (pin "D4") (pinfunction "GND_D4") (pintype "power_in"))
      (node (ref "D7") (pin "D7") (pinfunction "GND_D7") (pintype "power_in"))
      (node (ref "D7") (pin "E1") (pinfunction "GND_E1") (pintype "power_in"))
      (node (ref "D7") (pin "E10") (pinfunction "GND_E10") (pintype "power_in"))
      (node (ref "D7") (pin "E2") (pinfunction "MGTAVTT_E2") (pintype "power_in"))
      (node (ref "D7") (pin "E20") (pinfunction "GND_E20") (pintype "power_in"))
      (node (ref "D7") (pin "E3") (pinfunction "MGTXRXN1_115_E3") (pintype "input"))
      (node (ref "D7") (pin "E4") (pinfunction "MGTXRXP1_115_E4") (pintype "input"))
      (node (ref "D7") (pin "E5") (pinfunction "GND_E5") (pintype "power_in"))
      (node (ref "D7") (pin "E6") (pinfunction "MGTAVCC_E6") (pintype "power_in"))
      (node (ref "D7") (pin "E7") (pinfunction "GND_E7") (pintype "power_in"))
      (node (ref "D7") (pin "F17") (pinfunction "GND_F17") (pintype "power_in"))
      (node (ref "D7") (pin "F3") (pinfunction "GND_F3") (pintype "power_in"))
      (node (ref "D7") (pin "F4") (pinfunction "GND_F4") (pintype "power_in"))
      (node (ref "D7") (pin "F7") (pinfunction "GND_F7") (pintype "power_in"))
      (node (ref "D7") (pin "G1") (pinfunction "GND_G1") (pintype "power_in"))
      (node (ref "D7") (pin "G14") (pinfunction "GND_G14") (pintype "power_in"))
      (node (ref "D7") (pin "G2") (pinfunction "MGTAVTT_G2") (pintype "power_in"))
      (node (ref "D7") (pin "G3") (pinfunction "MGTXRXN0_115_G3") (pintype "input"))
      (node (ref "D7") (pin "G4") (pinfunction "MGTXRXP0_115_G4") (pintype "input"))
      (node (ref "D7") (pin "G5") (pinfunction "GND_G5") (pintype "power_in"))
      (node (ref "D7") (pin "G6") (pinfunction "MGTAVCC_G6") (pintype "power_in"))
      (node (ref "D7") (pin "H1") (pinfunction "MGTAVTTRCAL_115_H1") (pintype "passive"))
      (node (ref "D7") (pin "H11") (pinfunction "GND_H11") (pintype "power_in"))
      (node (ref "D7") (pin "H2") (pinfunction "MGTRREF_115_H2") (pintype "input"))
      (node (ref "D7") (pin "H21") (pinfunction "GND_H21") (pintype "power_in"))
      (node (ref "D7") (pin "H3") (pinfunction "GND_H3") (pintype "power_in"))
      (node (ref "D7") (pin "H4") (pinfunction "GND_H4") (pintype "power_in"))
      (node (ref "D7") (pin "H5") (pinfunction "GND_H5") (pintype "power_in"))
      (node (ref "D7") (pin "J1") (pinfunction "GND_J1") (pintype "power_in"))
      (node (ref "D7") (pin "J10") (pinfunction "GND_J10") (pintype "power_in"))
      (node (ref "D7") (pin "J12") (pinfunction "GND_J12") (pintype "power_in"))
      (node (ref "D7") (pin "J14") (pinfunction "GND_J14") (pintype "power_in"))
      (node (ref "D7") (pin "J18") (pinfunction "GND_J18") (pintype "power_in"))
      (node (ref "D7") (pin "J2") (pinfunction "GND_J2") (pintype "power_in"))
      (node (ref "D7") (pin "J3") (pinfunction "GND_J3") (pintype "power_in"))
      (node (ref "D7") (pin "J4") (pinfunction "MGTVCCAUX_J4") (pintype "power_in"))
      (node (ref "D7") (pin "J8") (pinfunction "GND_J8") (pintype "power_in"))
      (node (ref "D7") (pin "K11") (pinfunction "GNDADC_0_K11") (pintype "power_in"))
      (node (ref "D7") (pin "K13") (pinfunction "GND_K13") (pintype "power_in"))
      (node (ref "D7") (pin "K15") (pinfunction "GND_K15") (pintype "power_in"))
      (node (ref "D7") (pin "K5") (pinfunction "GND_K5") (pintype "power_in"))
      (node (ref "D7") (pin "K9") (pinfunction "GND_K9") (pintype "power_in"))
      (node (ref "D7") (pin "L10") (pinfunction "GND_L10") (pintype "power_in"))
      (node (ref "D7") (pin "L14") (pinfunction "GND_L14") (pintype "power_in"))
      (node (ref "D7") (pin "L2") (pinfunction "GND_L2") (pintype "power_in"))
      (node (ref "D7") (pin "L22") (pinfunction "GND_L22") (pintype "power_in"))
      (node (ref "D7") (pin "L8") (pinfunction "GND_L8") (pintype "power_in"))
      (node (ref "D7") (pin "M13") (pinfunction "GND_M13") (pintype "power_in"))
      (node (ref "D7") (pin "M15") (pinfunction "GND_M15") (pintype "power_in"))
      (node (ref "D7") (pin "M19") (pinfunction "GND_M19") (pintype "power_in"))
      (node (ref "D7") (pin "M9") (pinfunction "GND_M9") (pintype "power_in"))
      (node (ref "D7") (pin "N10") (pinfunction "GND_N10") (pintype "power_in"))
      (node (ref "D7") (pin "N14") (pinfunction "GND_N14") (pintype "power_in"))
      (node (ref "D7") (pin "N16") (pinfunction "GND_N16") (pintype "power_in"))
      (node (ref "D7") (pin "N6") (pinfunction "GND_N6") (pintype "power_in"))
      (node (ref "D7") (pin "N8") (pinfunction "GND_N8") (pintype "power_in"))
      (node (ref "D7") (pin "P11") (pinfunction "GND_P11") (pintype "power_in"))
      (node (ref "D7") (pin "P13") (pinfunction "GND_P13") (pintype "power_in"))
      (node (ref "D7") (pin "P15") (pinfunction "GND_P15") (pintype "power_in"))
      (node (ref "D7") (pin "P3") (pinfunction "GND_P3") (pintype "power_in"))
      (node (ref "D7") (pin "P7") (pinfunction "VCCBATT_0_P7") (pintype "power_in"))
      (node (ref "D7") (pin "P9") (pinfunction "GND_P9") (pintype "power_in"))
      (node (ref "D7") (pin "R10") (pinfunction "GND_R10") (pintype "power_in"))
      (node (ref "D7") (pin "R12") (pinfunction "GND_R12") (pintype "power_in"))
      (node (ref "D7") (pin "R14") (pinfunction "GND_R14") (pintype "power_in"))
      (node (ref "D7") (pin "R20") (pinfunction "GND_R20") (pintype "power_in"))
      (node (ref "D7") (pin "R8") (pinfunction "GND_R8") (pintype "power_in"))
      (node (ref "D7") (pin "T17") (pinfunction "GND_T17") (pintype "power_in"))
      (node (ref "D7") (pin "T7") (pinfunction "GND_T7") (pintype "power_in"))
      (node (ref "D7") (pin "U14") (pinfunction "GND_U14") (pintype "power_in"))
      (node (ref "D7") (pin "U4") (pinfunction "GND_U4") (pintype "power_in"))
      (node (ref "D7") (pin "V1") (pinfunction "GND_V1") (pintype "power_in"))
      (node (ref "D7") (pin "V11") (pinfunction "GND_V11") (pintype "power_in"))
      (node (ref "D7") (pin "V21") (pinfunction "GND_V21") (pintype "power_in"))
      (node (ref "D7") (pin "W18") (pinfunction "GND_W18") (pintype "power_in"))
      (node (ref "D7") (pin "W8") (pinfunction "GND_W8") (pintype "power_in"))
      (node (ref "D7") (pin "Y15") (pinfunction "GND_Y15") (pintype "power_in"))
      (node (ref "D7") (pin "Y5") (pinfunction "GND_Y5") (pintype "power_in"))
    )
    (net (code "12") (name "unconnected-(D7H-MGTREFCLK0N_115-PadD5)") (class "Default")
      (node (ref "D7") (pin "D5") (pinfunction "MGTREFCLK0N_115_D5") (pintype "input+no_connect"))
    )
    (net (code "13") (name "unconnected-(D7H-MGTREFCLK0P_115-PadD6)") (class "Default")
      (node (ref "D7") (pin "D6") (pinfunction "MGTREFCLK0P_115_D6") (pintype "input+no_connect"))
    )
    (net (code "14") (name "unconnected-(D7H-MGTREFCLK1N_115-PadF5)") (class "Default")
      (node (ref "D7") (pin "F5") (pinfunction "MGTREFCLK1N_115_F5") (pintype "input+no_connect"))
    )
    (net (code "15") (name "unconnected-(D7H-MGTREFCLK1P_115-PadF6)") (class "Default")
      (node (ref "D7") (pin "F6") (pinfunction "MGTREFCLK1P_115_F6") (pintype "input+no_connect"))
    )
    (net (code "16") (name "unconnected-(D7H-MGTXTXN0_115-PadF1)") (class "Default")
      (node (ref "D7") (pin "F1") (pinfunction "MGTXTXN0_115_F1") (pintype "output"))
    )
    (net (code "17") (name "unconnected-(D7H-MGTXTXN1_115-PadD1)") (class "Default")
      (node (ref "D7") (pin "D1") (pinfunction "MGTXTXN1_115_D1") (pintype "output"))
    )
    (net (code "18") (name "unconnected-(D7H-MGTXTXN2_115-PadB1)") (class "Default")
      (node (ref "D7") (pin "B1") (pinfunction "MGTXTXN2_115_B1") (pintype "output"))
    )
    (net (code "19") (name "unconnected-(D7H-MGTXTXN3_115-PadA3)") (class "Default")
      (node (ref "D7") (pin "A3") (pinfunction "MGTXTXN3_115_A3") (pintype "output"))
    )
    (net (code "20") (name "unconnected-(D7H-MGTXTXP0_115-PadF2)") (class "Default")
      (node (ref "D7") (pin "F2") (pinfunction "MGTXTXP0_115_F2") (pintype "output"))
    )
    (net (code "21") (name "unconnected-(D7H-MGTXTXP1_115-PadD2)") (class "Default")
      (node (ref "D7") (pin "D2") (pinfunction "MGTXTXP1_115_D2") (pintype "output"))
    )
    (net (code "22") (name "unconnected-(D7H-MGTXTXP2_115-PadB2)") (class "Default")
      (node (ref "D7") (pin "B2") (pinfunction "MGTXTXP2_115_B2") (pintype "output"))
    )
    (net (code "23") (name "unconnected-(D7H-MGTXTXP3_115-PadA4)") (class "Default")
      (node (ref "D7") (pin "A4") (pinfunction "MGTXTXP3_115_A4") (pintype "output"))
    )
  )
)
